# connections_to_beaglebone.net
KiCad netlist of a schematic drawn in Altium Designer
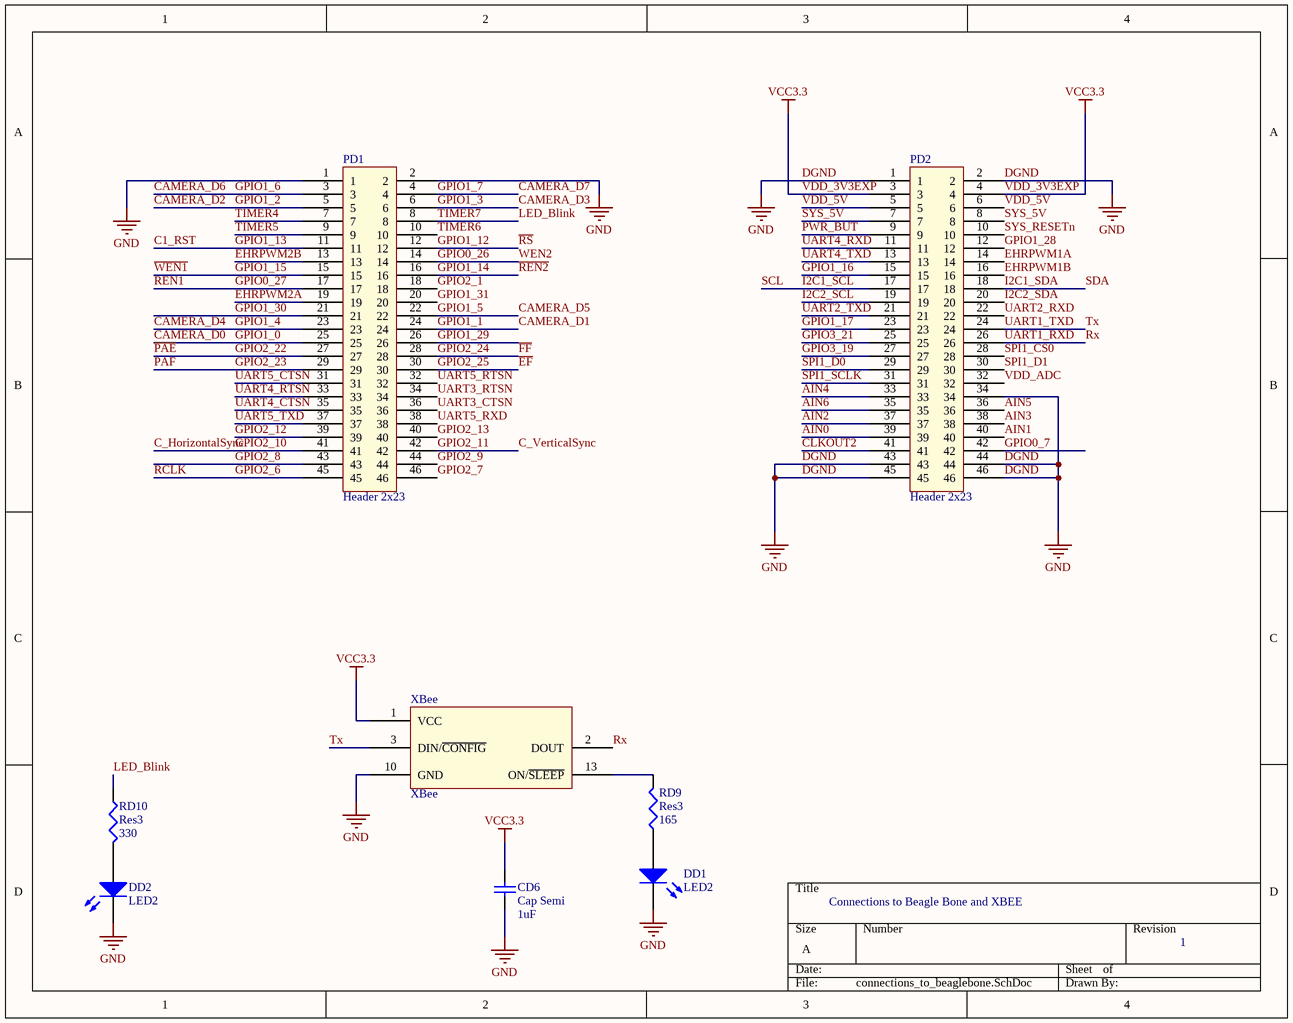
[diagram p0: connections_to_beaglebone.SchDoc]

(export (version "E")
  (design (tool "Eeschema 10.0.6"))
  (components
    (comp (ref "CD6")
      (value "Cap Semi")
      (footprint "CAPC1608L")
      (description "Capacitor (Semiconductor SIM Model)")
      (fields (field (name "ALTIUM_VALUE") "1uF") (field (name "PUBLISHER") "Altium Limited"))
      (libsource (lib "Miscellaneous Devices") (part "Cap Semi"))
    )
    (comp (ref "DD1")
      (value "LED2")
      (footprint "DIODE1608")
      (description "Typical RED, GREEN, YELLOW, AMBER GaAs LED")
      (fields (field (name "PUBLISHER") "Altium Limited"))
      (libsource (lib "") (part "LED2_1"))
    )
    (comp (ref "DD2")
      (value "LED2")
      (footprint "DIODE1608")
      (description "Typical RED, GREEN, YELLOW, AMBER GaAs LED")
      (fields (field (name "PUBLISHER") "Altium Limited"))
      (libsource (lib "Miscellaneous Devices") (part "LED2"))
    )
    (comp (ref "PD1")
      (value "Header 2x23")
      (footprint "HDR2X23")
      (libsource (lib "daughterboard") (part "Header 2x23"))
    )
    (comp (ref "PD2")
      (value "Header 2x23")
      (footprint "HDR2X23")
      (libsource (lib "daughterboard") (part "Header 2x23"))
    )
    (comp (ref "RD9")
      (value "Res3")
      (footprint "RESC1608L")
      (description "Resistor")
      (fields (field (name "ALTIUM_VALUE") "165") (field (name "PUBLISHER") "Altium Limited"))
      (libsource (lib "Miscellaneous Devices") (part "Res3"))
    )
    (comp (ref "RD10")
      (value "Res3")
      (footprint "RESC1608L")
      (description "Resistor")
      (fields (field (name "ALTIUM_VALUE") "330") (field (name "PUBLISHER") "Altium Limited"))
      (libsource (lib "") (part "Res3_1"))
    )
    (comp (ref "XBee")
      (value "XBee")
      (footprint "XBee")
      (description "XBee wireless transmitter/reveiver")
      (libsource (lib "daughterboard") (part "XBee"))
    )
  )
  (nets
    (net (code "1") (name "/AIN0") (class "Default")
      (node (ref "PD2") (pin "39") (pinfunction "39_39") (pintype "passive"))
    )
    (net (code "2") (name "/AIN1") (class "Default")
      (node (ref "PD2") (pin "40") (pinfunction "40_40") (pintype "passive"))
    )
    (net (code "3") (name "/AIN2") (class "Default")
      (node (ref "PD2") (pin "37") (pinfunction "37_37") (pintype "passive"))
    )
    (net (code "4") (name "/AIN3") (class "Default")
      (node (ref "PD2") (pin "38") (pinfunction "38_38") (pintype "passive"))
    )
    (net (code "5") (name "/AIN4") (class "Default")
      (node (ref "PD2") (pin "33") (pinfunction "33_33") (pintype "passive"))
    )
    (net (code "6") (name "/AIN5") (class "Default")
      (node (ref "PD2") (pin "36") (pinfunction "36_36") (pintype "passive"))
    )
    (net (code "7") (name "/AIN6") (class "Default")
      (node (ref "PD2") (pin "35") (pinfunction "35_35") (pintype "passive"))
    )
    (net (code "8") (name "/C1_RST") (class "Default")
      (node (ref "PD1") (pin "11") (pinfunction "11_11") (pintype "passive"))
    )
    (net (code "9") (name "/CAMERA_D0") (class "Default")
      (node (ref "PD1") (pin "25") (pinfunction "25_25") (pintype "passive"))
    )
    (net (code "10") (name "/CAMERA_D1") (class "Default")
      (node (ref "PD1") (pin "24") (pinfunction "24_24") (pintype "passive"))
    )
    (net (code "11") (name "/CAMERA_D2") (class "Default")
      (node (ref "PD1") (pin "5") (pinfunction "5_5") (pintype "passive"))
    )
    (net (code "12") (name "/CAMERA_D3") (class "Default")
      (node (ref "PD1") (pin "6") (pinfunction "6_6") (pintype "passive"))
    )
    (net (code "13") (name "/CAMERA_D4") (class "Default")
      (node (ref "PD1") (pin "23") (pinfunction "23_23") (pintype "passive"))
    )
    (net (code "14") (name "/CAMERA_D5") (class "Default")
      (node (ref "PD1") (pin "22") (pinfunction "22_22") (pintype "passive"))
    )
    (net (code "15") (name "/CAMERA_D6") (class "Default")
      (node (ref "PD1") (pin "3") (pinfunction "3_3") (pintype "passive"))
    )
    (net (code "16") (name "/CAMERA_D7") (class "Default")
      (node (ref "PD1") (pin "4") (pinfunction "4_4") (pintype "passive"))
    )
    (net (code "17") (name "/CLKOUT2") (class "Default")
      (node (ref "PD2") (pin "41") (pinfunction "41_41") (pintype "passive"))
    )
    (net (code "18") (name "/C_HorizontalSync") (class "Default")
      (node (ref "PD1") (pin "41") (pinfunction "41_41") (pintype "passive"))
    )
    (net (code "19") (name "/C_VerticalSync") (class "Default")
      (node (ref "PD1") (pin "42") (pinfunction "42_42") (pintype "passive"))
    )
    (net (code "20") (name "/EHRPWM1A") (class "Default")
      (node (ref "PD2") (pin "14") (pinfunction "14_14") (pintype "passive"))
    )
    (net (code "21") (name "/EHRPWM1B") (class "Default")
      (node (ref "PD2") (pin "16") (pinfunction "16_16") (pintype "passive"))
    )
    (net (code "22") (name "/EHRPWM2A") (class "Default")
      (node (ref "PD1") (pin "19") (pinfunction "19_19") (pintype "passive"))
    )
    (net (code "23") (name "/EHRPWM2B") (class "Default")
      (node (ref "PD1") (pin "13") (pinfunction "13_13") (pintype "passive"))
    )
    (net (code "24") (name "/GPIO0_7") (class "Default")
      (node (ref "PD2") (pin "42") (pinfunction "42_42") (pintype "passive"))
    )
    (net (code "25") (name "/GPIO0_26") (class "Default")
      (node (ref "PD1") (pin "14") (pinfunction "14_14") (pintype "passive"))
    )
    (net (code "26") (name "/GPIO0_27") (class "Default")
      (node (ref "PD1") (pin "17") (pinfunction "17_17") (pintype "passive"))
    )
    (net (code "27") (name "/GPIO1_12") (class "Default")
      (node (ref "PD1") (pin "12") (pinfunction "12_12") (pintype "passive"))
    )
    (net (code "28") (name "/GPIO1_14") (class "Default")
      (node (ref "PD1") (pin "16") (pinfunction "16_16") (pintype "passive"))
    )
    (net (code "29") (name "/GPIO1_15") (class "Default")
      (node (ref "PD1") (pin "15") (pinfunction "15_15") (pintype "passive"))
    )
    (net (code "30") (name "/GPIO1_16") (class "Default")
      (node (ref "PD2") (pin "15") (pinfunction "15_15") (pintype "passive"))
    )
    (net (code "31") (name "/GPIO1_17") (class "Default")
      (node (ref "PD2") (pin "23") (pinfunction "23_23") (pintype "passive"))
    )
    (net (code "32") (name "/GPIO1_28") (class "Default")
      (node (ref "PD2") (pin "12") (pinfunction "12_12") (pintype "passive"))
    )
    (net (code "33") (name "/GPIO1_29") (class "Default")
      (node (ref "PD1") (pin "26") (pinfunction "26_26") (pintype "passive"))
    )
    (net (code "34") (name "/GPIO1_30") (class "Default")
      (node (ref "PD1") (pin "21") (pinfunction "21_21") (pintype "passive"))
    )
    (net (code "35") (name "/GPIO1_31") (class "Default")
      (node (ref "PD1") (pin "20") (pinfunction "20_20") (pintype "passive"))
    )
    (net (code "36") (name "/GPIO2_1") (class "Default")
      (node (ref "PD1") (pin "18") (pinfunction "18_18") (pintype "passive"))
    )
    (net (code "37") (name "/GPIO2_6") (class "Default")
      (node (ref "PD1") (pin "45") (pinfunction "45_45") (pintype "passive"))
    )
    (net (code "38") (name "/GPIO2_7") (class "Default")
      (node (ref "PD1") (pin "46") (pinfunction "46_46") (pintype "passive"))
    )
    (net (code "39") (name "/GPIO2_8") (class "Default")
      (node (ref "PD1") (pin "43") (pinfunction "43_43") (pintype "passive"))
    )
    (net (code "40") (name "/GPIO2_9") (class "Default")
      (node (ref "PD1") (pin "44") (pinfunction "44_44") (pintype "passive"))
    )
    (net (code "41") (name "/GPIO2_12") (class "Default")
      (node (ref "PD1") (pin "39") (pinfunction "39_39") (pintype "passive"))
    )
    (net (code "42") (name "/GPIO2_13") (class "Default")
      (node (ref "PD1") (pin "40") (pinfunction "40_40") (pintype "passive"))
    )
    (net (code "43") (name "/GPIO2_22") (class "Default")
      (node (ref "PD1") (pin "27") (pinfunction "27_27") (pintype "passive"))
    )
    (net (code "44") (name "/GPIO2_23") (class "Default")
      (node (ref "PD1") (pin "29") (pinfunction "29_29") (pintype "passive"))
    )
    (net (code "45") (name "/GPIO2_24") (class "Default")
      (node (ref "PD1") (pin "28") (pinfunction "28_28") (pintype "passive"))
    )
    (net (code "46") (name "/GPIO2_25") (class "Default")
      (node (ref "PD1") (pin "30") (pinfunction "30_30") (pintype "passive"))
    )
    (net (code "47") (name "/GPIO3_19") (class "Default")
      (node (ref "PD2") (pin "27") (pinfunction "27_27") (pintype "passive"))
    )
    (net (code "48") (name "/GPIO3_21") (class "Default")
      (node (ref "PD2") (pin "25") (pinfunction "25_25") (pintype "passive"))
    )
    (net (code "49") (name "/I2C1_SCL") (class "Default")
      (node (ref "PD2") (pin "17") (pinfunction "17_17") (pintype "passive"))
    )
    (net (code "50") (name "/I2C1_SDA") (class "Default")
      (node (ref "PD2") (pin "18") (pinfunction "18_18") (pintype "passive"))
    )
    (net (code "51") (name "/I2C2_SCL") (class "Default")
      (node (ref "PD2") (pin "19") (pinfunction "19_19") (pintype "passive"))
    )
    (net (code "52") (name "/I2C2_SDA") (class "Default")
      (node (ref "PD2") (pin "20") (pinfunction "20_20") (pintype "passive"))
    )
    (net (code "53") (name "/LED_Blink") (class "Default")
      (node (ref "PD1") (pin "8") (pinfunction "8_8") (pintype "passive"))
      (node (ref "RD10") (pin "2") (pinfunction "2_2") (pintype "passive"))
    )
    (net (code "54") (name "/PWR_BUT") (class "Default")
      (node (ref "PD2") (pin "9") (pinfunction "9_9") (pintype "passive"))
    )
    (net (code "55") (name "/Rx") (class "Default")
      (node (ref "PD2") (pin "26") (pinfunction "26_26") (pintype "passive"))
      (node (ref "XBee") (pin "2") (pinfunction "DOUT_2") (pintype "passive"))
    )
    (net (code "56") (name "/SPI1_CS0") (class "Default")
      (node (ref "PD2") (pin "28") (pinfunction "28_28") (pintype "passive"))
    )
    (net (code "57") (name "/SPI1_D0") (class "Default")
      (node (ref "PD2") (pin "29") (pinfunction "29_29") (pintype "passive"))
    )
    (net (code "58") (name "/SPI1_D1") (class "Default")
      (node (ref "PD2") (pin "30") (pinfunction "30_30") (pintype "passive"))
    )
    (net (code "59") (name "/SPI1_SCLK") (class "Default")
      (node (ref "PD2") (pin "31") (pinfunction "31_31") (pintype "passive"))
    )
    (net (code "60") (name "/SYS_5V") (class "Default")
      (node (ref "PD2") (pin "7") (pinfunction "7_7") (pintype "passive"))
      (node (ref "PD2") (pin "8") (pinfunction "8_8") (pintype "passive"))
    )
    (net (code "61") (name "/SYS_RESETn") (class "Default")
      (node (ref "PD2") (pin "10") (pinfunction "10_10") (pintype "passive"))
    )
    (net (code "62") (name "/TIMER4") (class "Default")
      (node (ref "PD1") (pin "7") (pinfunction "7_7") (pintype "passive"))
    )
    (net (code "63") (name "/TIMER5") (class "Default")
      (node (ref "PD1") (pin "9") (pinfunction "9_9") (pintype "passive"))
    )
    (net (code "64") (name "/TIMER6") (class "Default")
      (node (ref "PD1") (pin "10") (pinfunction "10_10") (pintype "passive"))
    )
    (net (code "65") (name "/Tx") (class "Default")
      (node (ref "PD2") (pin "24") (pinfunction "24_24") (pintype "passive"))
      (node (ref "XBee") (pin "3") (pinfunction "DIN/~{CONFIG}_3") (pintype "passive"))
    )
    (net (code "66") (name "/UART2_RXD") (class "Default")
      (node (ref "PD2") (pin "22") (pinfunction "22_22") (pintype "passive"))
    )
    (net (code "67") (name "/UART2_TXD") (class "Default")
      (node (ref "PD2") (pin "21") (pinfunction "21_21") (pintype "passive"))
    )
    (net (code "68") (name "/UART3_CTSN") (class "Default")
      (node (ref "PD1") (pin "36") (pinfunction "36_36") (pintype "passive"))
    )
    (net (code "69") (name "/UART3_RTSN") (class "Default")
      (node (ref "PD1") (pin "34") (pinfunction "34_34") (pintype "passive"))
    )
    (net (code "70") (name "/UART4_CTSN") (class "Default")
      (node (ref "PD1") (pin "35") (pinfunction "35_35") (pintype "passive"))
    )
    (net (code "71") (name "/UART4_RTSN") (class "Default")
      (node (ref "PD1") (pin "33") (pinfunction "33_33") (pintype "passive"))
    )
    (net (code "72") (name "/UART4_RXD") (class "Default")
      (node (ref "PD2") (pin "11") (pinfunction "11_11") (pintype "passive"))
    )
    (net (code "73") (name "/UART4_TXD") (class "Default")
      (node (ref "PD2") (pin "13") (pinfunction "13_13") (pintype "passive"))
    )
    (net (code "74") (name "/UART5_CTSN") (class "Default")
      (node (ref "PD1") (pin "31") (pinfunction "31_31") (pintype "passive"))
    )
    (net (code "75") (name "/UART5_RTSN") (class "Default")
      (node (ref "PD1") (pin "32") (pinfunction "32_32") (pintype "passive"))
    )
    (net (code "76") (name "/UART5_RXD") (class "Default")
      (node (ref "PD1") (pin "38") (pinfunction "38_38") (pintype "passive"))
    )
    (net (code "77") (name "/UART5_TXD") (class "Default")
      (node (ref "PD1") (pin "37") (pinfunction "37_37") (pintype "passive"))
    )
    (net (code "78") (name "/VDD_5V") (class "Default")
      (node (ref "PD2") (pin "5") (pinfunction "5_5") (pintype "passive"))
      (node (ref "PD2") (pin "6") (pinfunction "6_6") (pintype "passive"))
    )
    (net (code "79") (name "/VDD_ADC") (class "Default")
      (node (ref "PD2") (pin "32") (pinfunction "32_32") (pintype "passive"))
    )
    (net (code "80") (name "GND") (class "Default")
      (node (ref "CD6") (pin "1") (pinfunction "1_1") (pintype "passive"))
      (node (ref "DD1") (pin "2") (pinfunction "K_2") (pintype "passive"))
      (node (ref "DD2") (pin "2") (pinfunction "K_2") (pintype "passive"))
      (node (ref "PD1") (pin "1") (pinfunction "1_1") (pintype "passive"))
      (node (ref "PD1") (pin "2") (pinfunction "2_2") (pintype "passive"))
      (node (ref "PD2") (pin "1") (pinfunction "1_1") (pintype "passive"))
      (node (ref "PD2") (pin "2") (pinfunction "2_2") (pintype "passive"))
      (node (ref "PD2") (pin "34") (pinfunction "34_34") (pintype "passive"))
      (node (ref "PD2") (pin "43") (pinfunction "43_43") (pintype "passive"))
      (node (ref "PD2") (pin "44") (pinfunction "44_44") (pintype "passive"))
      (node (ref "PD2") (pin "45") (pinfunction "45_45") (pintype "passive"))
      (node (ref "PD2") (pin "46") (pinfunction "46_46") (pintype "passive"))
      (node (ref "XBee") (pin "10") (pinfunction "GND_10") (pintype "passive"))
    )
    (net (code "81") (name "Net-(DD1-A)") (class "Default")
      (node (ref "DD1") (pin "1") (pinfunction "A_1") (pintype "passive"))
      (node (ref "RD9") (pin "1") (pinfunction "1_1") (pintype "passive"))
    )
    (net (code "82") (name "Net-(DD2-A)") (class "Default")
      (node (ref "DD2") (pin "1") (pinfunction "A_1") (pintype "passive"))
      (node (ref "RD10") (pin "1") (pinfunction "1_1") (pintype "passive"))
    )
    (net (code "83") (name "Net-(XBee-ON{slash}~{SLEEP})") (class "Default")
      (node (ref "RD9") (pin "2") (pinfunction "2_2") (pintype "passive"))
      (node (ref "XBee") (pin "13") (pinfunction "ON/~{SLEEP}_13") (pintype "passive"))
    )
    (net (code "84") (name "VCC3.3") (class "Default")
      (node (ref "CD6") (pin "2") (pinfunction "2_2") (pintype "passive"))
      (node (ref "PD2") (pin "3") (pinfunction "3_3") (pintype "passive"))
      (node (ref "PD2") (pin "4") (pinfunction "4_4") (pintype "passive"))
      (node (ref "XBee") (pin "1") (pinfunction "VCC_1") (pintype "passive"))
    )
    (net (code "85") (name "unconnected-(XBee-AD0{slash}DIO0-Pad20)") (class "Default")
      (node (ref "XBee") (pin "20") (pinfunction "AD0/DIO0_20") (pintype "passive"))
    )
    (net (code "86") (name "unconnected-(XBee-AD1{slash}DIO1-Pad19)") (class "Default")
      (node (ref "XBee") (pin "19") (pinfunction "AD1/DIO1_19") (pintype "passive"))
    )
    (net (code "87") (name "unconnected-(XBee-AD2{slash}DIO2-Pad18)") (class "Default")
      (node (ref "XBee") (pin "18") (pinfunction "AD2/DIO2_18") (pintype "passive"))
    )
    (net (code "88") (name "unconnected-(XBee-AD3{slash}DIO3-Pad17)") (class "Default")
      (node (ref "XBee") (pin "17") (pinfunction "AD3/DIO3_17") (pintype "passive"))
    )
    (net (code "89") (name "unconnected-(XBee-AD4{slash}DIO4-Pad11)") (class "Default")
      (node (ref "XBee") (pin "11") (pinfunction "AD4/DIO4_11") (pintype "passive"))
    )
    (net (code "90") (name "unconnected-(XBee-Associate{slash}AD5{slash}DIO5-Pad15)") (class "Default")
      (node (ref "XBee") (pin "15") (pinfunction "Associate/AD5/DIO5_15") (pintype "passive"))
    )
    (net (code "91") (name "unconnected-(XBee-D08-Pad4)") (class "Default")
      (node (ref "XBee") (pin "4") (pinfunction "D08_4") (pintype "passive"))
    )
    (net (code "92") (name "unconnected-(XBee-PWM0{slash}RSSI-Pad6)") (class "Default")
      (node (ref "XBee") (pin "6") (pinfunction "PWM0/RSSI_6") (pintype "passive"))
    )
    (net (code "93") (name "unconnected-(XBee-PWM1-Pad7)") (class "Default")
      (node (ref "XBee") (pin "7") (pinfunction "PWM1_7") (pintype "passive"))
    )
    (net (code "94") (name "unconnected-(XBee-VREF-Pad14)") (class "Default")
      (node (ref "XBee") (pin "14") (pinfunction "VREF_14") (pintype "passive"))
    )
    (net (code "95") (name "unconnected-(XBee-[reserved]-Pad8)") (class "Default")
      (node (ref "XBee") (pin "8") (pinfunction "[reserved]_8") (pintype "passive"))
    )
    (net (code "96") (name "unconnected-(XBee-~{CTS}{slash}DIO7-Pad12)") (class "Default")
      (node (ref "XBee") (pin "12") (pinfunction "~{CTS}/DIO7_12") (pintype "passive"))
    )
    (net (code "97") (name "unconnected-(XBee-~{DTR}{slash}SLEEP_RQ{slash}DI8-Pad9)") (class "Default")
      (node (ref "XBee") (pin "9") (pinfunction "~{DTR}/SLEEP_RQ/DI8_9") (pintype "passive"))
    )
    (net (code "98") (name "unconnected-(XBee-~{RESET}-Pad5)") (class "Default")
      (node (ref "XBee") (pin "5") (pinfunction "~{RESET}_5") (pintype "passive"))
    )
    (net (code "99") (name "unconnected-(XBee-~{RTS}{slash}AD6{slash}DIO6-Pad16)") (class "Default")
      (node (ref "XBee") (pin "16") (pinfunction "~{RTS}/AD6/DIO6_16") (pintype "passive"))
    )
  )
)
